# ARE_adaptadora_dsPIC30F4011_44qfn.net
KiCad netlist of a schematic drawn in EAGLE
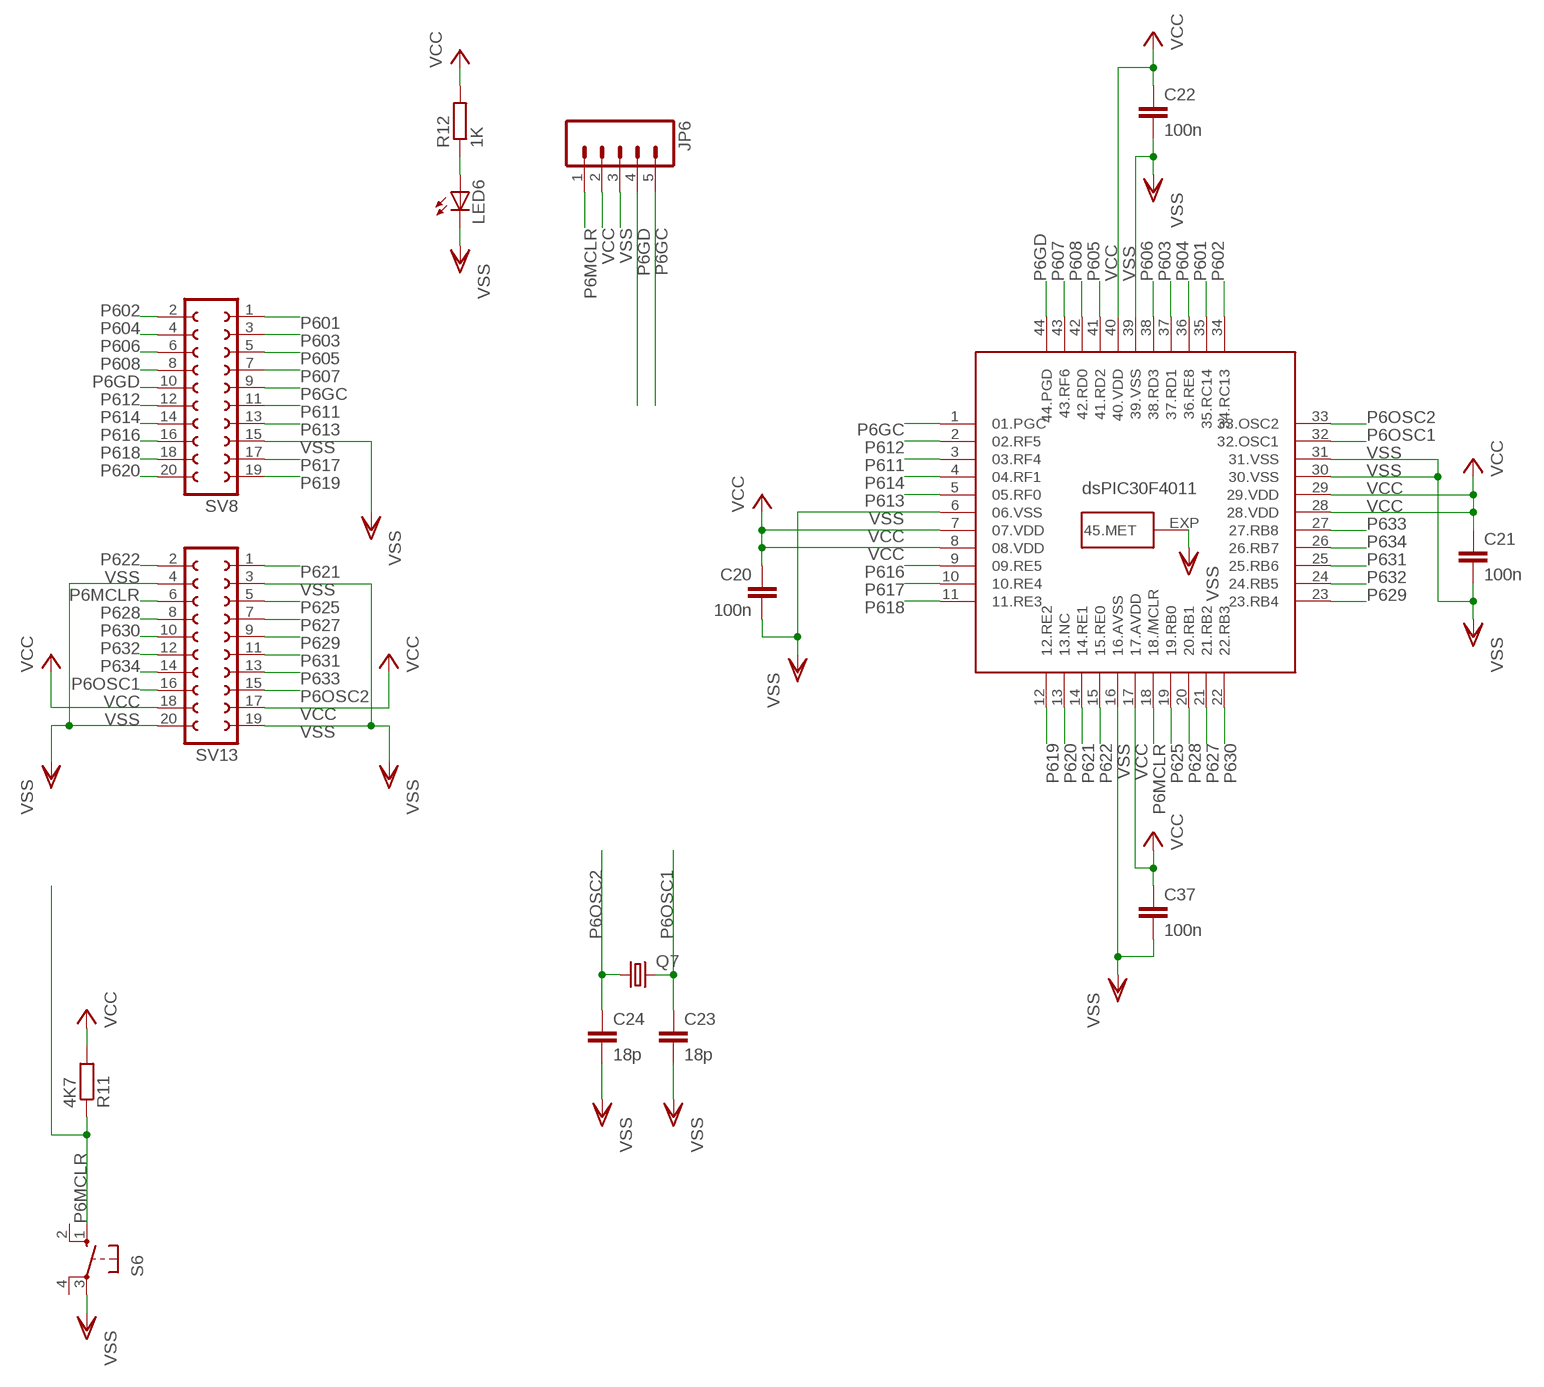
[diagram p0: schematic, sheet 1]

(export (version "E")
  (design (tool "Eeschema 10.0.6"))
  (components
    (comp (ref "C20")
      (value "100n")
      (footprint "eagle-import:C0805")
      (libsource (lib "eagle-import") (part "C-EUC0805"))
    )
    (comp (ref "C21")
      (value "100n")
      (footprint "eagle-import:C0805")
      (libsource (lib "eagle-import") (part "C-EUC0805"))
    )
    (comp (ref "C22")
      (value "100n")
      (footprint "eagle-import:C0805")
      (libsource (lib "eagle-import") (part "C-EUC0805"))
    )
    (comp (ref "C23")
      (value "18p")
      (footprint "eagle-import:C0805")
      (libsource (lib "eagle-import") (part "C-EUC0805"))
    )
    (comp (ref "C24")
      (value "18p")
      (footprint "eagle-import:C0805")
      (libsource (lib "eagle-import") (part "C-EUC0805"))
    )
    (comp (ref "C37")
      (value "100n")
      (footprint "eagle-import:C0805")
      (libsource (lib "eagle-import") (part "C-EUC0805"))
    )
    (comp (ref "JP6")
      (value "M05PTH")
      (footprint "eagle-import:1X05")
      (libsource (lib "eagle-import") (part "M05PTH"))
    )
    (comp (ref "LED6")
      (value "LEDCHIPLED_0805")
      (footprint "eagle-import:CHIPLED_0805")
      (libsource (lib "eagle-import") (part "LEDCHIPLED_0805"))
    )
    (comp (ref "Q7")
      (value "CRYSTALHC18U-V")
      (footprint "eagle-import:HC18U-V")
      (libsource (lib "eagle-import") (part "CRYSTALHC18U-V"))
    )
    (comp (ref "R11")
      (value "4K7")
      (footprint "eagle-import:R0805")
      (libsource (lib "eagle-import") (part "R-EU_R0805"))
    )
    (comp (ref "R12")
      (value "1K")
      (footprint "eagle-import:R0805")
      (libsource (lib "eagle-import") (part "R-EU_R0805"))
    )
    (comp (ref "S6")
      (value "10-XX")
      (footprint "eagle-import:B3F-10XX")
      (fields
        (field (name "MPN") "B3F-1000")
        (field (name "MPN_1") "B3F-1000")
        (field (name "OC_FARNELL") "176432")
        (field (name "OC_NEWARK") "36M3542")
      )
      (libsource (lib "eagle-import") (part "10-XX"))
    )
    (comp (ref "SV8")
      (value "FE10-2W")
      (footprint "eagle-import:FE10-2W")
      (libsource (lib "eagle-import") (part "FE10-2W"))
    )
    (comp (ref "SV13")
      (value "FE10-2W")
      (footprint "eagle-import:FE10-2W")
      (libsource (lib "eagle-import") (part "FE10-2W"))
    )
    (comp (ref "U$2")
      (value "DSPIC30F4011")
      (footprint "eagle-import:QFN44ML8X8")
      (libsource (lib "eagle-import") (part "DSPIC30F4011"))
    )
  )
  (nets
    (net (code "1") (name "/P6GC") (class "Default")
      (node (ref "JP6") (pin "5") (pinfunction "5_5") (pintype "passive"))
      (node (ref "SV8") (pin "9") (pinfunction "9_9") (pintype "passive"))
      (node (ref "U$2") (pin "1") (pinfunction "01.PGC_1") (pintype "bidirectional"))
    )
    (net (code "2") (name "/P6GD") (class "Default")
      (node (ref "JP6") (pin "4") (pinfunction "4_4") (pintype "passive"))
      (node (ref "SV8") (pin "10") (pinfunction "10_10") (pintype "passive"))
      (node (ref "U$2") (pin "44") (pinfunction "44.PGD_44") (pintype "bidirectional"))
    )
    (net (code "3") (name "/P6MCLR") (class "Default")
      (node (ref "JP6") (pin "1") (pinfunction "1_1") (pintype "passive"))
      (node (ref "R11") (pin "1") (pinfunction "1_1") (pintype "passive"))
      (node (ref "S6") (pin "1") (pinfunction "S_1") (pintype "passive"))
      (node (ref "SV13") (pin "6") (pinfunction "6_6") (pintype "passive"))
      (node (ref "U$2") (pin "18") (pinfunction "18./MCLR_18") (pintype "bidirectional"))
    )
    (net (code "4") (name "/P6OSC1") (class "Default")
      (node (ref "C23") (pin "1") (pinfunction "1_1") (pintype "passive"))
      (node (ref "Q7") (pin "2") (pinfunction "2_2") (pintype "passive"))
      (node (ref "SV13") (pin "16") (pinfunction "16_16") (pintype "passive"))
      (node (ref "U$2") (pin "32") (pinfunction "32.OSC1_32") (pintype "bidirectional"))
    )
    (net (code "5") (name "/P6OSC2") (class "Default")
      (node (ref "C24") (pin "1") (pinfunction "1_1") (pintype "passive"))
      (node (ref "Q7") (pin "1") (pinfunction "1_1") (pintype "passive"))
      (node (ref "SV13") (pin "15") (pinfunction "15_15") (pintype "passive"))
      (node (ref "U$2") (pin "33") (pinfunction "33.OSC2_33") (pintype "bidirectional"))
    )
    (net (code "6") (name "/P601") (class "Default")
      (node (ref "SV8") (pin "1") (pinfunction "1_1") (pintype "passive"))
      (node (ref "U$2") (pin "35") (pinfunction "35.RC14_35") (pintype "bidirectional"))
    )
    (net (code "7") (name "/P602") (class "Default")
      (node (ref "SV8") (pin "2") (pinfunction "2_2") (pintype "passive"))
      (node (ref "U$2") (pin "34") (pinfunction "34.RC13_34") (pintype "bidirectional"))
    )
    (net (code "8") (name "/P603") (class "Default")
      (node (ref "SV8") (pin "3") (pinfunction "3_3") (pintype "passive"))
      (node (ref "U$2") (pin "37") (pinfunction "37.RD1_37") (pintype "bidirectional"))
    )
    (net (code "9") (name "/P604") (class "Default")
      (node (ref "SV8") (pin "4") (pinfunction "4_4") (pintype "passive"))
      (node (ref "U$2") (pin "36") (pinfunction "36.RE8_36") (pintype "bidirectional"))
    )
    (net (code "10") (name "/P605") (class "Default")
      (node (ref "SV8") (pin "5") (pinfunction "5_5") (pintype "passive"))
      (node (ref "U$2") (pin "41") (pinfunction "41.RD2_41") (pintype "bidirectional"))
    )
    (net (code "11") (name "/P606") (class "Default")
      (node (ref "SV8") (pin "6") (pinfunction "6_6") (pintype "passive"))
      (node (ref "U$2") (pin "38") (pinfunction "38.RD3_38") (pintype "bidirectional"))
    )
    (net (code "12") (name "/P607") (class "Default")
      (node (ref "SV8") (pin "7") (pinfunction "7_7") (pintype "passive"))
      (node (ref "U$2") (pin "43") (pinfunction "43.RF6_43") (pintype "bidirectional"))
    )
    (net (code "13") (name "/P608") (class "Default")
      (node (ref "SV8") (pin "8") (pinfunction "8_8") (pintype "passive"))
      (node (ref "U$2") (pin "42") (pinfunction "42.RD0_42") (pintype "bidirectional"))
    )
    (net (code "14") (name "/P611") (class "Default")
      (node (ref "SV8") (pin "11") (pinfunction "11_11") (pintype "passive"))
      (node (ref "U$2") (pin "3") (pinfunction "03.RF4_3") (pintype "bidirectional"))
    )
    (net (code "15") (name "/P612") (class "Default")
      (node (ref "SV8") (pin "12") (pinfunction "12_12") (pintype "passive"))
      (node (ref "U$2") (pin "2") (pinfunction "02.RF5_2") (pintype "bidirectional"))
    )
    (net (code "16") (name "/P613") (class "Default")
      (node (ref "SV8") (pin "13") (pinfunction "13_13") (pintype "passive"))
      (node (ref "U$2") (pin "5") (pinfunction "05.RF0_5") (pintype "bidirectional"))
    )
    (net (code "17") (name "/P614") (class "Default")
      (node (ref "SV8") (pin "14") (pinfunction "14_14") (pintype "passive"))
      (node (ref "U$2") (pin "4") (pinfunction "04.RF1_4") (pintype "bidirectional"))
    )
    (net (code "18") (name "/P616") (class "Default")
      (node (ref "SV8") (pin "16") (pinfunction "16_16") (pintype "passive"))
      (node (ref "U$2") (pin "9") (pinfunction "09.RE5_9") (pintype "bidirectional"))
    )
    (net (code "19") (name "/P617") (class "Default")
      (node (ref "SV8") (pin "17") (pinfunction "17_17") (pintype "passive"))
      (node (ref "U$2") (pin "10") (pinfunction "10.RE4_10") (pintype "bidirectional"))
    )
    (net (code "20") (name "/P618") (class "Default")
      (node (ref "SV8") (pin "18") (pinfunction "18_18") (pintype "passive"))
      (node (ref "U$2") (pin "11") (pinfunction "11.RE3_11") (pintype "bidirectional"))
    )
    (net (code "21") (name "/P619") (class "Default")
      (node (ref "SV8") (pin "19") (pinfunction "19_19") (pintype "passive"))
      (node (ref "U$2") (pin "12") (pinfunction "12.RE2_12") (pintype "bidirectional"))
    )
    (net (code "22") (name "/P620") (class "Default")
      (node (ref "SV8") (pin "20") (pinfunction "20_20") (pintype "passive"))
      (node (ref "U$2") (pin "13") (pinfunction "13.NC_13") (pintype "bidirectional"))
    )
    (net (code "23") (name "/P621") (class "Default")
      (node (ref "SV13") (pin "1") (pinfunction "1_1") (pintype "passive"))
      (node (ref "U$2") (pin "14") (pinfunction "14.RE1_14") (pintype "bidirectional"))
    )
    (net (code "24") (name "/P622") (class "Default")
      (node (ref "SV13") (pin "2") (pinfunction "2_2") (pintype "passive"))
      (node (ref "U$2") (pin "15") (pinfunction "15.RE0_15") (pintype "bidirectional"))
    )
    (net (code "25") (name "/P625") (class "Default")
      (node (ref "SV13") (pin "5") (pinfunction "5_5") (pintype "passive"))
      (node (ref "U$2") (pin "19") (pinfunction "19.RB0_19") (pintype "bidirectional"))
    )
    (net (code "26") (name "/P627") (class "Default")
      (node (ref "SV13") (pin "7") (pinfunction "7_7") (pintype "passive"))
      (node (ref "U$2") (pin "21") (pinfunction "21.RB2_21") (pintype "bidirectional"))
    )
    (net (code "27") (name "/P628") (class "Default")
      (node (ref "SV13") (pin "8") (pinfunction "8_8") (pintype "passive"))
      (node (ref "U$2") (pin "20") (pinfunction "20.RB1_20") (pintype "bidirectional"))
    )
    (net (code "28") (name "/P629") (class "Default")
      (node (ref "SV13") (pin "9") (pinfunction "9_9") (pintype "passive"))
      (node (ref "U$2") (pin "23") (pinfunction "23.RB4_23") (pintype "bidirectional"))
    )
    (net (code "29") (name "/P630") (class "Default")
      (node (ref "SV13") (pin "10") (pinfunction "10_10") (pintype "passive"))
      (node (ref "U$2") (pin "22") (pinfunction "22.RB3_22") (pintype "bidirectional"))
    )
    (net (code "30") (name "/P631") (class "Default")
      (node (ref "SV13") (pin "11") (pinfunction "11_11") (pintype "passive"))
      (node (ref "U$2") (pin "25") (pinfunction "25.RB6_25") (pintype "bidirectional"))
    )
    (net (code "31") (name "/P632") (class "Default")
      (node (ref "SV13") (pin "12") (pinfunction "12_12") (pintype "passive"))
      (node (ref "U$2") (pin "24") (pinfunction "24.RB5_24") (pintype "bidirectional"))
    )
    (net (code "32") (name "/P633") (class "Default")
      (node (ref "SV13") (pin "13") (pinfunction "13_13") (pintype "passive"))
      (node (ref "U$2") (pin "27") (pinfunction "27.RB8_27") (pintype "bidirectional"))
    )
    (net (code "33") (name "/P634") (class "Default")
      (node (ref "SV13") (pin "14") (pinfunction "14_14") (pintype "passive"))
      (node (ref "U$2") (pin "26") (pinfunction "26.RB7_26") (pintype "bidirectional"))
    )
    (net (code "34") (name "Net-(LED6-PadA)") (class "Default")
      (node (ref "LED6") (pin "A") (pinfunction "A_A") (pintype "passive"))
      (node (ref "R12") (pin "1") (pinfunction "1_1") (pintype "passive"))
    )
    (net (code "35") (name "VCC") (class "Default")
      (node (ref "C20") (pin "1") (pinfunction "1_1") (pintype "passive"))
      (node (ref "C21") (pin "1") (pinfunction "1_1") (pintype "passive"))
      (node (ref "C22") (pin "1") (pinfunction "1_1") (pintype "passive"))
      (node (ref "C37") (pin "1") (pinfunction "1_1") (pintype "passive"))
      (node (ref "JP6") (pin "2") (pinfunction "2_2") (pintype "passive"))
      (node (ref "R11") (pin "2") (pinfunction "2_2") (pintype "passive"))
      (node (ref "R12") (pin "2") (pinfunction "2_2") (pintype "passive"))
      (node (ref "SV13") (pin "17") (pinfunction "17_17") (pintype "passive"))
      (node (ref "SV13") (pin "18") (pinfunction "18_18") (pintype "passive"))
      (node (ref "U$2") (pin "17") (pinfunction "17.AVDD_17") (pintype "bidirectional"))
      (node (ref "U$2") (pin "28") (pinfunction "28.VDD_28") (pintype "bidirectional"))
      (node (ref "U$2") (pin "29") (pinfunction "29.VDD_29") (pintype "bidirectional"))
      (node (ref "U$2") (pin "40") (pinfunction "40.VDD_40") (pintype "bidirectional"))
      (node (ref "U$2") (pin "7") (pinfunction "07.VDD_7") (pintype "bidirectional"))
      (node (ref "U$2") (pin "8") (pinfunction "08.VDD_8") (pintype "bidirectional"))
    )
    (net (code "36") (name "VSS") (class "Default")
      (node (ref "C20") (pin "2") (pinfunction "2_2") (pintype "passive"))
      (node (ref "C21") (pin "2") (pinfunction "2_2") (pintype "passive"))
      (node (ref "C22") (pin "2") (pinfunction "2_2") (pintype "passive"))
      (node (ref "C23") (pin "2") (pinfunction "2_2") (pintype "passive"))
      (node (ref "C24") (pin "2") (pinfunction "2_2") (pintype "passive"))
      (node (ref "C37") (pin "2") (pinfunction "2_2") (pintype "passive"))
      (node (ref "JP6") (pin "3") (pinfunction "3_3") (pintype "passive"))
      (node (ref "LED6") (pin "C") (pinfunction "C_C") (pintype "passive"))
      (node (ref "S6") (pin "3") (pinfunction "P_3") (pintype "passive"))
      (node (ref "SV13") (pin "19") (pinfunction "19_19") (pintype "passive"))
      (node (ref "SV13") (pin "20") (pinfunction "20_20") (pintype "passive"))
      (node (ref "SV13") (pin "3") (pinfunction "3_3") (pintype "passive"))
      (node (ref "SV13") (pin "4") (pinfunction "4_4") (pintype "passive"))
      (node (ref "SV8") (pin "15") (pinfunction "15_15") (pintype "passive"))
      (node (ref "U$2") (pin "16") (pinfunction "16.AVSS_16") (pintype "bidirectional"))
      (node (ref "U$2") (pin "30") (pinfunction "30.VSS_30") (pintype "bidirectional"))
      (node (ref "U$2") (pin "31") (pinfunction "31.VSS_31") (pintype "bidirectional"))
      (node (ref "U$2") (pin "39") (pinfunction "39.VSS_39") (pintype "bidirectional"))
      (node (ref "U$2") (pin "6") (pinfunction "06.VSS_6") (pintype "bidirectional"))
      (node (ref "U$2") (pin "EXP") (pinfunction "45.MET_EXP") (pintype "bidirectional"))
    )
    (net (code "37") (name "unconnected-(S6-P1-Pad4)") (class "Default")
      (node (ref "S6") (pin "4") (pinfunction "P1_4") (pintype "passive"))
    )
    (net (code "38") (name "unconnected-(S6-S1-Pad2)") (class "Default")
      (node (ref "S6") (pin "2") (pinfunction "S1_2") (pintype "passive"))
    )
  )
)
